# CONNECTOR_EXP.net
KiCad netlist of a schematic drawn in Altium Designer
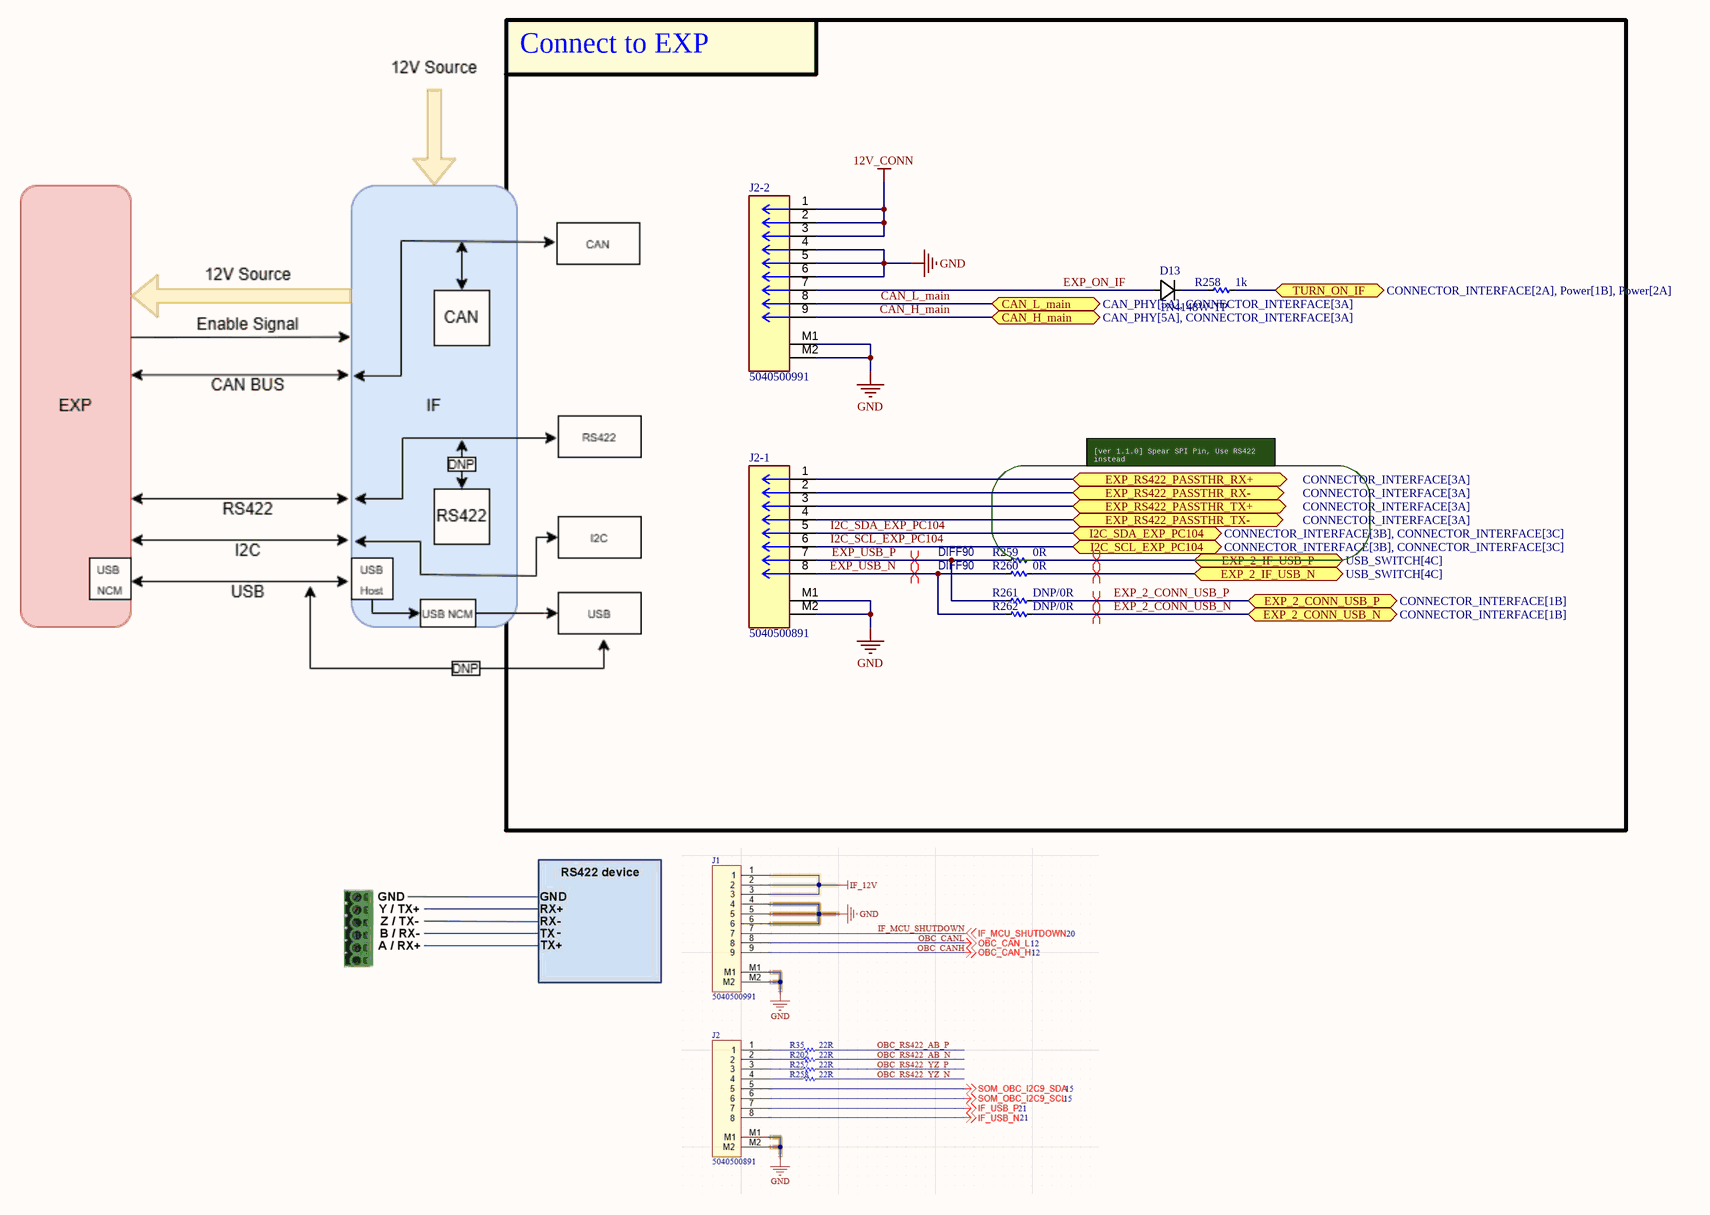
[diagram p0: CONNECTOR_EXP.SchDoc]

(export (version "E")
  (design (tool "Eeschema 10.0.6"))
  (components
    (comp (ref "D13")
      (value "1N4148W-TP")
      (footprint "SOD123_MCC")
      (description "Description")
      (fields (field (name "COPYRIGHT") "Copyright (C) 2026 Ultra Librarian. All rights reserved."))
      (libsource (lib "IFBschelib") (part "1N4148W-TP"))
    )
    (comp (ref "J2-1")
      (value "5040500891")
      (footprint "MOLEX_5040500891")
      (description "Connector Header Surface Mount, Right Angle 8 position 0.059\" (1.50mm)`")
      (libsource (lib "IFBschelib") (part "5040500891"))
    )
    (comp (ref "J2-2")
      (value "5040500991")
      (footprint "MOLEX_5040500991")
      (description "Connector Header Surface Mount, Right Angle 9 position 0.059\" (1.50mm)")
      (libsource (lib "IFBschelib") (part "5040500991"))
    )
    (comp (ref "R258")
      (value "1k")
      (footprint "RES_C_1005x30_L")
      (description "RES")
      (libsource (lib "LABLIB") (part "_RES_B_2"))
    )
    (comp (ref "R259")
      (value "0R")
      (footprint "RES_C_1005x30_L")
      (description "RES")
      (libsource (lib "LABLIB") (part "_RES_B_2"))
    )
    (comp (ref "R260")
      (value "0R")
      (footprint "RES_C_1005x30_L")
      (description "RES")
      (libsource (lib "LABLIB") (part "_RES_B_2"))
    )
    (comp (ref "R261")
      (value "DNP/0R")
      (footprint "RES_C_1005x30_L")
      (description "RES")
      (libsource (lib "IFBschelib") (part "_RES_B_2"))
    )
    (comp (ref "R262")
      (value "DNP/0R")
      (footprint "RES_C_1005x30_L")
      (description "RES")
      (libsource (lib "IFBschelib") (part "_RES_B_2"))
    )
  )
  (nets
    (net (code "1") (name "/CAN_H_main") (class "Default")
      (node (ref "J2-2") (pin "9") (pinfunction "9_9") (pintype "passive"))
    )
    (net (code "2") (name "/CAN_L_main") (class "Default")
      (node (ref "J2-2") (pin "8") (pinfunction "8_8") (pintype "passive"))
    )
    (net (code "3") (name "/EXP_2_CONN_USB_N") (class "Default")
      (node (ref "R262") (pin "2") (pinfunction "2_2") (pintype "passive"))
    )
    (net (code "4") (name "/EXP_2_CONN_USB_P") (class "Default")
      (node (ref "R261") (pin "2") (pinfunction "2_2") (pintype "passive"))
    )
    (net (code "5") (name "/EXP_2_IF_USB_N") (class "Default")
      (node (ref "R260") (pin "2") (pinfunction "2_2") (pintype "passive"))
    )
    (net (code "6") (name "/EXP_2_IF_USB_P") (class "Default")
      (node (ref "R259") (pin "2") (pinfunction "2_2") (pintype "passive"))
    )
    (net (code "7") (name "/EXP_ON_IF") (class "Default")
      (node (ref "D13") (pin "2") (pinfunction "2_2") (pintype "passive"))
      (node (ref "J2-2") (pin "7") (pinfunction "7_7") (pintype "passive"))
    )
    (net (code "8") (name "/EXP_RS422_PASSTHR_RX+") (class "Default")
      (node (ref "J2-1") (pin "1") (pinfunction "1_1") (pintype "passive"))
    )
    (net (code "9") (name "/EXP_RS422_PASSTHR_RX-") (class "Default")
      (node (ref "J2-1") (pin "2") (pinfunction "2_2") (pintype "passive"))
    )
    (net (code "10") (name "/EXP_RS422_PASSTHR_TX+") (class "Default")
      (node (ref "J2-1") (pin "3") (pinfunction "3_3") (pintype "passive"))
    )
    (net (code "11") (name "/EXP_RS422_PASSTHR_TX-") (class "Default")
      (node (ref "J2-1") (pin "4") (pinfunction "4_4") (pintype "passive"))
    )
    (net (code "12") (name "/EXP_USB_N") (class "Default")
      (node (ref "J2-1") (pin "8") (pinfunction "8_8") (pintype "passive"))
      (node (ref "R260") (pin "1") (pinfunction "1_1") (pintype "passive"))
      (node (ref "R262") (pin "1") (pinfunction "1_1") (pintype "passive"))
    )
    (net (code "13") (name "/EXP_USB_P") (class "Default")
      (node (ref "J2-1") (pin "7") (pinfunction "7_7") (pintype "passive"))
      (node (ref "R259") (pin "1") (pinfunction "1_1") (pintype "passive"))
      (node (ref "R261") (pin "1") (pinfunction "1_1") (pintype "passive"))
    )
    (net (code "14") (name "/I2C_SCL_EXP_PC104") (class "Default")
      (node (ref "J2-1") (pin "6") (pinfunction "6_6") (pintype "passive"))
    )
    (net (code "15") (name "/I2C_SDA_EXP_PC104") (class "Default")
      (node (ref "J2-1") (pin "5") (pinfunction "5_5") (pintype "passive"))
    )
    (net (code "16") (name "/TURN_ON_IF") (class "Default")
      (node (ref "R258") (pin "2") (pinfunction "2_2") (pintype "passive"))
    )
    (net (code "17") (name "12V_CONN") (class "Default")
      (node (ref "J2-2") (pin "1") (pinfunction "1_1") (pintype "passive"))
      (node (ref "J2-2") (pin "2") (pinfunction "2_2") (pintype "passive"))
      (node (ref "J2-2") (pin "3") (pinfunction "3_3") (pintype "passive"))
    )
    (net (code "18") (name "GND") (class "Default")
      (node (ref "J2-1") (pin "M1") (pinfunction "M1_M1") (pintype "passive"))
      (node (ref "J2-1") (pin "M2") (pinfunction "M2_M2") (pintype "passive"))
      (node (ref "J2-2") (pin "4") (pinfunction "4_4") (pintype "passive"))
      (node (ref "J2-2") (pin "5") (pinfunction "5_5") (pintype "passive"))
      (node (ref "J2-2") (pin "6") (pinfunction "6_6") (pintype "passive"))
      (node (ref "J2-2") (pin "M1") (pinfunction "M1_M1") (pintype "passive"))
      (node (ref "J2-2") (pin "M2") (pinfunction "M2_M2") (pintype "passive"))
    )
    (net (code "19") (name "Net-(D13-Pad1)") (class "Default")
      (node (ref "D13") (pin "1") (pinfunction "1_1") (pintype "passive"))
      (node (ref "R258") (pin "1") (pinfunction "1_1") (pintype "passive"))
    )
  )
)
